# 2_waffling60-MXHS-ISO_matrix.net
KiCad netlist of a schematic drawn in Altium Designer
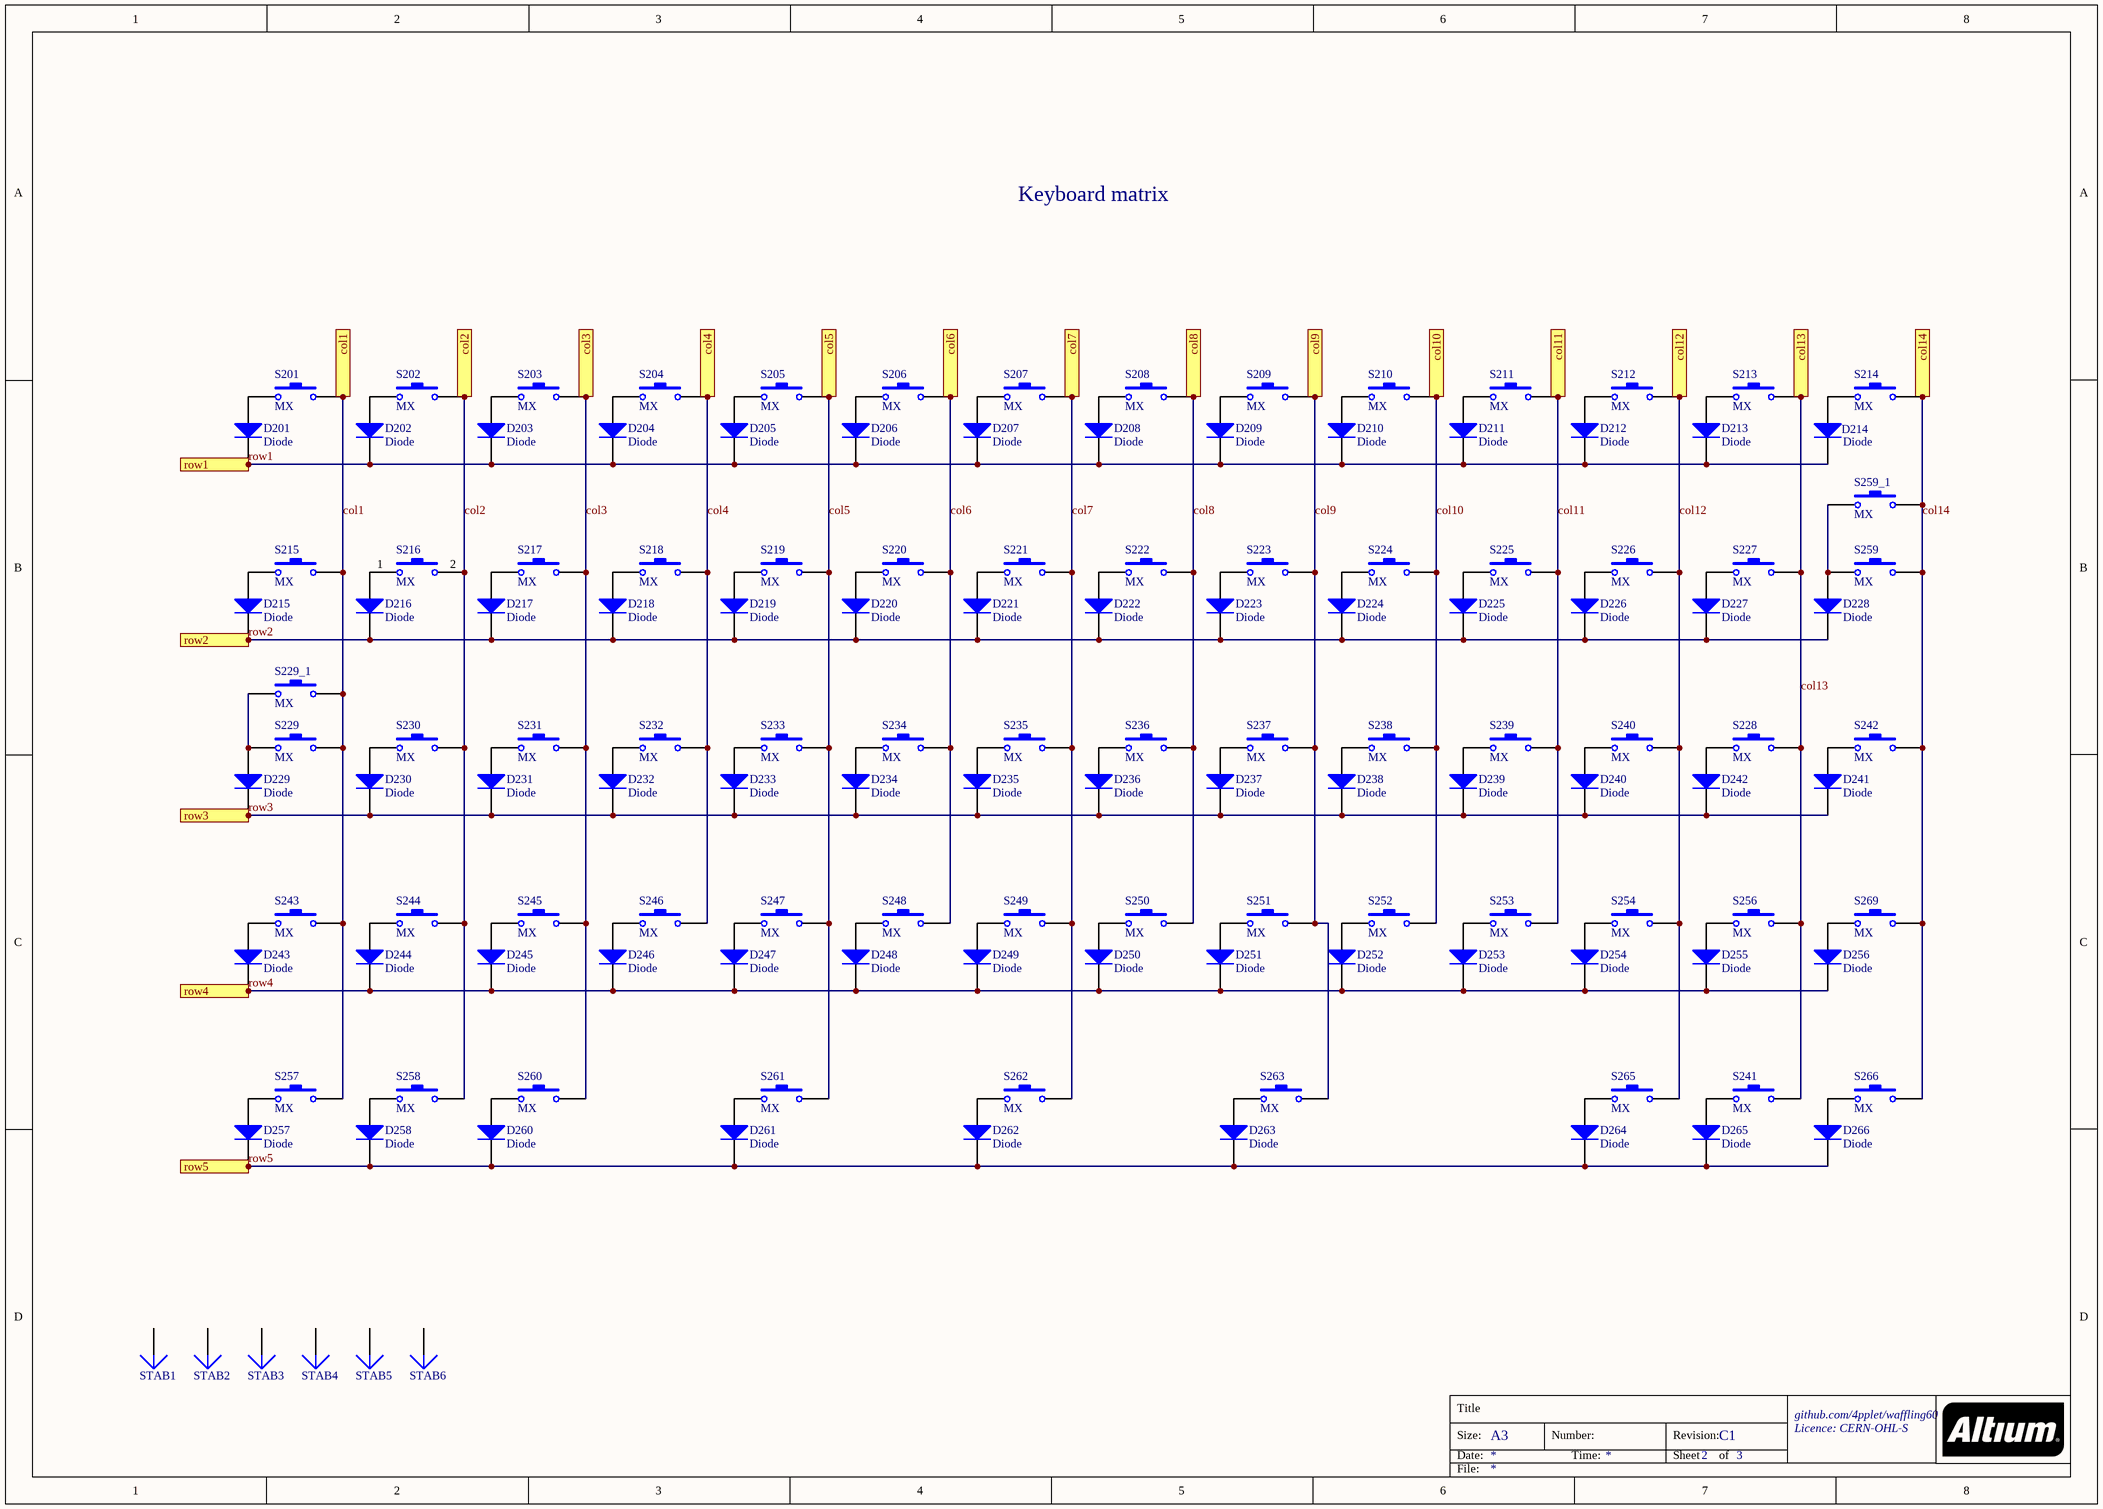
[diagram p0: 2_waffling60-MXHS-ISO_matrix.SchDoc]

(export (version "E")
  (design (tool "Eeschema 10.0.6"))
  (components
    (comp (ref "D201")
      (value "Diode")
      (footprint "SOD-123")
      (description "Default Diode")
      (fields (field (name "LCSC PART #") "C81598") (field (name "MRF.PART") "1N4148W"))
      (libsource (lib "Miscellaneous Devices") (part "Diode"))
    )
    (comp (ref "D202")
      (value "Diode")
      (footprint "SOD-123")
      (description "Default Diode")
      (fields (field (name "LCSC PART #") "C81598") (field (name "MRF.PART") "1N4148W"))
      (libsource (lib "Miscellaneous Devices") (part "Diode"))
    )
    (comp (ref "D203")
      (value "Diode")
      (footprint "SOD-123")
      (description "Default Diode")
      (fields (field (name "LCSC PART #") "C81598") (field (name "MRF.PART") "1N4148W"))
      (libsource (lib "Miscellaneous Devices") (part "Diode"))
    )
    (comp (ref "D204")
      (value "Diode")
      (footprint "SOD-123")
      (description "Default Diode")
      (fields (field (name "LCSC PART #") "C81598") (field (name "MRF.PART") "1N4148W"))
      (libsource (lib "Miscellaneous Devices") (part "Diode"))
    )
    (comp (ref "D205")
      (value "Diode")
      (footprint "SOD-123")
      (description "Default Diode")
      (fields (field (name "LCSC PART #") "C81598") (field (name "MRF.PART") "1N4148W"))
      (libsource (lib "Miscellaneous Devices") (part "Diode"))
    )
    (comp (ref "D206")
      (value "Diode")
      (footprint "SOD-123")
      (description "Default Diode")
      (fields (field (name "LCSC PART #") "C81598") (field (name "MRF.PART") "1N4148W"))
      (libsource (lib "Miscellaneous Devices") (part "Diode"))
    )
    (comp (ref "D207")
      (value "Diode")
      (footprint "SOD-123")
      (description "Default Diode")
      (fields (field (name "LCSC PART #") "C81598") (field (name "MRF.PART") "1N4148W"))
      (libsource (lib "Miscellaneous Devices") (part "Diode"))
    )
    (comp (ref "D208")
      (value "Diode")
      (footprint "SOD-123")
      (description "Default Diode")
      (fields (field (name "LCSC PART #") "C81598") (field (name "MRF.PART") "1N4148W"))
      (libsource (lib "Miscellaneous Devices") (part "Diode"))
    )
    (comp (ref "D209")
      (value "Diode")
      (footprint "SOD-123")
      (description "Default Diode")
      (fields (field (name "LCSC PART #") "C81598") (field (name "MRF.PART") "1N4148W"))
      (libsource (lib "Miscellaneous Devices") (part "Diode"))
    )
    (comp (ref "D210")
      (value "Diode")
      (footprint "SOD-123")
      (description "Default Diode")
      (fields (field (name "LCSC PART #") "C81598") (field (name "MRF.PART") "1N4148W"))
      (libsource (lib "Miscellaneous Devices") (part "Diode"))
    )
    (comp (ref "D211")
      (value "Diode")
      (footprint "SOD-123")
      (description "Default Diode")
      (fields (field (name "LCSC PART #") "C81598") (field (name "MRF.PART") "1N4148W"))
      (libsource (lib "Miscellaneous Devices") (part "Diode"))
    )
    (comp (ref "D212")
      (value "Diode")
      (footprint "SOD-123")
      (description "Default Diode")
      (fields (field (name "LCSC PART #") "C81598") (field (name "MRF.PART") "1N4148W"))
      (libsource (lib "Miscellaneous Devices") (part "Diode"))
    )
    (comp (ref "D213")
      (value "Diode")
      (footprint "SOD-123")
      (description "Default Diode")
      (fields (field (name "LCSC PART #") "C81598") (field (name "MRF.PART") "1N4148W"))
      (libsource (lib "Miscellaneous Devices") (part "Diode"))
    )
    (comp (ref "D214")
      (value "Diode")
      (footprint "SOD-123")
      (description "Default Diode")
      (fields (field (name "LCSC PART #") "C81598") (field (name "MRF.PART") "1N4148W"))
      (libsource (lib "Miscellaneous Devices") (part "Diode"))
    )
    (comp (ref "D215")
      (value "Diode")
      (footprint "SOD-123")
      (description "Default Diode")
      (fields (field (name "LCSC PART #") "C81598") (field (name "MRF.PART") "1N4148W"))
      (libsource (lib "Miscellaneous Devices") (part "Diode"))
    )
    (comp (ref "D216")
      (value "Diode")
      (footprint "SOD-123")
      (description "Default Diode")
      (fields (field (name "LCSC PART #") "C81598") (field (name "MRF.PART") "1N4148W"))
      (libsource (lib "Miscellaneous Devices") (part "Diode"))
    )
    (comp (ref "D217")
      (value "Diode")
      (footprint "SOD-123")
      (description "Default Diode")
      (fields (field (name "LCSC PART #") "C81598") (field (name "MRF.PART") "1N4148W"))
      (libsource (lib "Miscellaneous Devices") (part "Diode"))
    )
    (comp (ref "D218")
      (value "Diode")
      (footprint "SOD-123")
      (description "Default Diode")
      (fields (field (name "LCSC PART #") "C81598") (field (name "MRF.PART") "1N4148W"))
      (libsource (lib "Miscellaneous Devices") (part "Diode"))
    )
    (comp (ref "D219")
      (value "Diode")
      (footprint "SOD-123")
      (description "Default Diode")
      (fields (field (name "LCSC PART #") "C81598") (field (name "MRF.PART") "1N4148W"))
      (libsource (lib "Miscellaneous Devices") (part "Diode"))
    )
    (comp (ref "D220")
      (value "Diode")
      (footprint "SOD-123")
      (description "Default Diode")
      (fields (field (name "LCSC PART #") "C81598") (field (name "MRF.PART") "1N4148W"))
      (libsource (lib "Miscellaneous Devices") (part "Diode"))
    )
    (comp (ref "D221")
      (value "Diode")
      (footprint "SOD-123")
      (description "Default Diode")
      (fields (field (name "LCSC PART #") "C81598") (field (name "MRF.PART") "1N4148W"))
      (libsource (lib "Miscellaneous Devices") (part "Diode"))
    )
    (comp (ref "D222")
      (value "Diode")
      (footprint "SOD-123")
      (description "Default Diode")
      (fields (field (name "LCSC PART #") "C81598") (field (name "MRF.PART") "1N4148W"))
      (libsource (lib "Miscellaneous Devices") (part "Diode"))
    )
    (comp (ref "D223")
      (value "Diode")
      (footprint "SOD-123")
      (description "Default Diode")
      (fields (field (name "LCSC PART #") "C81598") (field (name "MRF.PART") "1N4148W"))
      (libsource (lib "Miscellaneous Devices") (part "Diode"))
    )
    (comp (ref "D224")
      (value "Diode")
      (footprint "SOD-123")
      (description "Default Diode")
      (fields (field (name "LCSC PART #") "C81598") (field (name "MRF.PART") "1N4148W"))
      (libsource (lib "Miscellaneous Devices") (part "Diode"))
    )
    (comp (ref "D225")
      (value "Diode")
      (footprint "SOD-123")
      (description "Default Diode")
      (fields (field (name "LCSC PART #") "C81598") (field (name "MRF.PART") "1N4148W"))
      (libsource (lib "Miscellaneous Devices") (part "Diode"))
    )
    (comp (ref "D226")
      (value "Diode")
      (footprint "SOD-123")
      (description "Default Diode")
      (fields (field (name "LCSC PART #") "C81598") (field (name "MRF.PART") "1N4148W"))
      (libsource (lib "Miscellaneous Devices") (part "Diode"))
    )
    (comp (ref "D227")
      (value "Diode")
      (footprint "SOD-123")
      (description "Default Diode")
      (fields (field (name "LCSC PART #") "C81598") (field (name "MRF.PART") "1N4148W"))
      (libsource (lib "Miscellaneous Devices") (part "Diode"))
    )
    (comp (ref "D228")
      (value "Diode")
      (footprint "SOD-123")
      (description "Default Diode")
      (fields (field (name "LCSC PART #") "C81598") (field (name "MRF.PART") "1N4148W"))
      (libsource (lib "Miscellaneous Devices") (part "Diode"))
    )
    (comp (ref "D229")
      (value "Diode")
      (footprint "SOD-123")
      (description "Default Diode")
      (fields (field (name "LCSC PART #") "C81598") (field (name "MRF.PART") "1N4148W"))
      (libsource (lib "Miscellaneous Devices") (part "Diode"))
    )
    (comp (ref "D230")
      (value "Diode")
      (footprint "SOD-123")
      (description "Default Diode")
      (fields (field (name "LCSC PART #") "C81598") (field (name "MRF.PART") "1N4148W"))
      (libsource (lib "Miscellaneous Devices") (part "Diode"))
    )
    (comp (ref "D231")
      (value "Diode")
      (footprint "SOD-123")
      (description "Default Diode")
      (fields (field (name "LCSC PART #") "C81598") (field (name "MRF.PART") "1N4148W"))
      (libsource (lib "Miscellaneous Devices") (part "Diode"))
    )
    (comp (ref "D232")
      (value "Diode")
      (footprint "SOD-123")
      (description "Default Diode")
      (fields (field (name "LCSC PART #") "C81598") (field (name "MRF.PART") "1N4148W"))
      (libsource (lib "Miscellaneous Devices") (part "Diode"))
    )
    (comp (ref "D233")
      (value "Diode")
      (footprint "SOD-123")
      (description "Default Diode")
      (fields (field (name "LCSC PART #") "C81598") (field (name "MRF.PART") "1N4148W"))
      (libsource (lib "Miscellaneous Devices") (part "Diode"))
    )
    (comp (ref "D234")
      (value "Diode")
      (footprint "SOD-123")
      (description "Default Diode")
      (fields (field (name "LCSC PART #") "C81598") (field (name "MRF.PART") "1N4148W"))
      (libsource (lib "Miscellaneous Devices") (part "Diode"))
    )
    (comp (ref "D235")
      (value "Diode")
      (footprint "SOD-123")
      (description "Default Diode")
      (fields (field (name "LCSC PART #") "C81598") (field (name "MRF.PART") "1N4148W"))
      (libsource (lib "Miscellaneous Devices") (part "Diode"))
    )
    (comp (ref "D236")
      (value "Diode")
      (footprint "SOD-123")
      (description "Default Diode")
      (fields (field (name "LCSC PART #") "C81598") (field (name "MRF.PART") "1N4148W"))
      (libsource (lib "Miscellaneous Devices") (part "Diode"))
    )
    (comp (ref "D237")
      (value "Diode")
      (footprint "SOD-123")
      (description "Default Diode")
      (fields (field (name "LCSC PART #") "C81598") (field (name "MRF.PART") "1N4148W"))
      (libsource (lib "Miscellaneous Devices") (part "Diode"))
    )
    (comp (ref "D238")
      (value "Diode")
      (footprint "SOD-123")
      (description "Default Diode")
      (fields (field (name "LCSC PART #") "C81598") (field (name "MRF.PART") "1N4148W"))
      (libsource (lib "Miscellaneous Devices") (part "Diode"))
    )
    (comp (ref "D239")
      (value "Diode")
      (footprint "SOD-123")
      (description "Default Diode")
      (fields (field (name "LCSC PART #") "C81598") (field (name "MRF.PART") "1N4148W"))
      (libsource (lib "Miscellaneous Devices") (part "Diode"))
    )
    (comp (ref "D240")
      (value "Diode")
      (footprint "SOD-123")
      (description "Default Diode")
      (fields (field (name "LCSC PART #") "C81598") (field (name "MRF.PART") "1N4148W"))
      (libsource (lib "Miscellaneous Devices") (part "Diode"))
    )
    (comp (ref "D241")
      (value "Diode")
      (footprint "SOD-123")
      (description "Default Diode")
      (fields (field (name "LCSC PART #") "C81598") (field (name "MRF.PART") "1N4148W"))
      (libsource (lib "Miscellaneous Devices") (part "Diode"))
    )
    (comp (ref "D242")
      (value "Diode")
      (footprint "SOD-123")
      (description "Default Diode")
      (fields (field (name "LCSC PART #") "C81598") (field (name "MRF.PART") "1N4148W"))
      (libsource (lib "Miscellaneous Devices") (part "Diode"))
    )
    (comp (ref "D243")
      (value "Diode")
      (footprint "SOD-123")
      (description "Default Diode")
      (fields (field (name "LCSC PART #") "C81598") (field (name "MRF.PART") "1N4148W"))
      (libsource (lib "Miscellaneous Devices") (part "Diode"))
    )
    (comp (ref "D244")
      (value "Diode")
      (footprint "SOD-123")
      (description "Default Diode")
      (fields (field (name "LCSC PART #") "C81598") (field (name "MRF.PART") "1N4148W"))
      (libsource (lib "Miscellaneous Devices") (part "Diode"))
    )
    (comp (ref "D245")
      (value "Diode")
      (footprint "SOD-123")
      (description "Default Diode")
      (fields (field (name "LCSC PART #") "C81598") (field (name "MRF.PART") "1N4148W"))
      (libsource (lib "Miscellaneous Devices") (part "Diode"))
    )
    (comp (ref "D246")
      (value "Diode")
      (footprint "SOD-123")
      (description "Default Diode")
      (fields (field (name "LCSC PART #") "C81598") (field (name "MRF.PART") "1N4148W"))
      (libsource (lib "Miscellaneous Devices") (part "Diode"))
    )
    (comp (ref "D247")
      (value "Diode")
      (footprint "SOD-123")
      (description "Default Diode")
      (fields (field (name "LCSC PART #") "C81598") (field (name "MRF.PART") "1N4148W"))
      (libsource (lib "Miscellaneous Devices") (part "Diode"))
    )
    (comp (ref "D248")
      (value "Diode")
      (footprint "SOD-123")
      (description "Default Diode")
      (fields (field (name "LCSC PART #") "C81598") (field (name "MRF.PART") "1N4148W"))
      (libsource (lib "Miscellaneous Devices") (part "Diode"))
    )
    (comp (ref "D249")
      (value "Diode")
      (footprint "SOD-123")
      (description "Default Diode")
      (fields (field (name "LCSC PART #") "C81598") (field (name "MRF.PART") "1N4148W"))
      (libsource (lib "Miscellaneous Devices") (part "Diode"))
    )
    (comp (ref "D250")
      (value "Diode")
      (footprint "SOD-123")
      (description "Default Diode")
      (fields (field (name "LCSC PART #") "C81598") (field (name "MRF.PART") "1N4148W"))
      (libsource (lib "Miscellaneous Devices") (part "Diode"))
    )
    (comp (ref "D251")
      (value "Diode")
      (footprint "SOD-123")
      (description "Default Diode")
      (fields (field (name "LCSC PART #") "C81598") (field (name "MRF.PART") "1N4148W"))
      (libsource (lib "Miscellaneous Devices") (part "Diode"))
    )
    (comp (ref "D252")
      (value "Diode")
      (footprint "SOD-123")
      (description "Default Diode")
      (fields (field (name "LCSC PART #") "C81598") (field (name "MRF.PART") "1N4148W"))
      (libsource (lib "Miscellaneous Devices") (part "Diode"))
    )
    (comp (ref "D253")
      (value "Diode")
      (footprint "SOD-123")
      (description "Default Diode")
      (fields (field (name "LCSC PART #") "C81598") (field (name "MRF.PART") "1N4148W"))
      (libsource (lib "Miscellaneous Devices") (part "Diode"))
    )
    (comp (ref "D254")
      (value "Diode")
      (footprint "SOD-123")
      (description "Default Diode")
      (fields (field (name "LCSC PART #") "C81598") (field (name "MRF.PART") "1N4148W"))
      (libsource (lib "Miscellaneous Devices") (part "Diode"))
    )
    (comp (ref "D255")
      (value "Diode")
      (footprint "SOD-123")
      (description "Default Diode")
      (fields (field (name "LCSC PART #") "C81598") (field (name "MRF.PART") "1N4148W"))
      (libsource (lib "Miscellaneous Devices") (part "Diode"))
    )
    (comp (ref "D256")
      (value "Diode")
      (footprint "SOD-123")
      (description "Default Diode")
      (fields (field (name "LCSC PART #") "C81598") (field (name "MRF.PART") "1N4148W"))
      (libsource (lib "Miscellaneous Devices") (part "Diode"))
    )
    (comp (ref "D257")
      (value "Diode")
      (footprint "SOD-123")
      (description "Default Diode")
      (fields (field (name "LCSC PART #") "C81598") (field (name "MRF.PART") "1N4148W"))
      (libsource (lib "Miscellaneous Devices") (part "Diode"))
    )
    (comp (ref "D258")
      (value "Diode")
      (footprint "SOD-123")
      (description "Default Diode")
      (fields (field (name "LCSC PART #") "C81598") (field (name "MRF.PART") "1N4148W"))
      (libsource (lib "Miscellaneous Devices") (part "Diode"))
    )
    (comp (ref "D260")
      (value "Diode")
      (footprint "SOD-123")
      (description "Default Diode")
      (fields (field (name "LCSC PART #") "C81598") (field (name "MRF.PART") "1N4148W"))
      (libsource (lib "Miscellaneous Devices") (part "Diode"))
    )
    (comp (ref "D261")
      (value "Diode")
      (footprint "SOD-123")
      (description "Default Diode")
      (fields (field (name "LCSC PART #") "C81598") (field (name "MRF.PART") "1N4148W"))
      (libsource (lib "Miscellaneous Devices") (part "Diode"))
    )
    (comp (ref "D262")
      (value "Diode")
      (footprint "SOD-123")
      (description "Default Diode")
      (fields (field (name "LCSC PART #") "C81598") (field (name "MRF.PART") "1N4148W"))
      (libsource (lib "Miscellaneous Devices") (part "Diode"))
    )
    (comp (ref "D263")
      (value "Diode")
      (footprint "SOD-123")
      (description "Default Diode")
      (fields (field (name "LCSC PART #") "C81598") (field (name "MRF.PART") "1N4148W"))
      (libsource (lib "Miscellaneous Devices") (part "Diode"))
    )
    (comp (ref "D264")
      (value "Diode")
      (footprint "SOD-123")
      (description "Default Diode")
      (fields (field (name "LCSC PART #") "C81598") (field (name "MRF.PART") "1N4148W"))
      (libsource (lib "Miscellaneous Devices") (part "Diode"))
    )
    (comp (ref "D265")
      (value "Diode")
      (footprint "SOD-123")
      (description "Default Diode")
      (fields (field (name "LCSC PART #") "C81598") (field (name "MRF.PART") "1N4148W"))
      (libsource (lib "Miscellaneous Devices") (part "Diode"))
    )
    (comp (ref "D266")
      (value "Diode")
      (footprint "SOD-123")
      (description "Default Diode")
      (fields (field (name "LCSC PART #") "C81598") (field (name "MRF.PART") "1N4148W"))
      (libsource (lib "Miscellaneous Devices") (part "Diode"))
    )
    (comp (ref "S201")
      (value "MX")
      (footprint "MXHS-switch - 1U Top layer - AS2")
      (description "Switch")
      (fields (field (name "LCSC PART #") "C2803348") (field (name "MRF.PART") "CPG151101S11"))
      (libsource (lib "Miscellaneous Devices") (part "SW-PB"))
    )
    (comp (ref "S202")
      (value "MX")
      (footprint "MXHS-switch - 1U Top layer - switched pol AS2")
      (description "Switch")
      (fields (field (name "LCSC PART #") "C2803348") (field (name "MRF.PART") "CPG151101S11"))
      (libsource (lib "Miscellaneous Devices") (part "SW-PB"))
    )
    (comp (ref "S203")
      (value "MX")
      (footprint "MXHS-switch - 1U Top layer - AS2")
      (description "Switch")
      (fields (field (name "LCSC PART #") "C2803348") (field (name "MRF.PART") "CPG151101S11"))
      (libsource (lib "Miscellaneous Devices") (part "SW-PB"))
    )
    (comp (ref "S204")
      (value "MX")
      (footprint "MXHS-switch - 1U Top layer - switched pol AS2")
      (description "Switch")
      (fields (field (name "LCSC PART #") "C2803348") (field (name "MRF.PART") "CPG151101S11"))
      (libsource (lib "Miscellaneous Devices") (part "SW-PB"))
    )
    (comp (ref "S205")
      (value "MX")
      (footprint "MXHS-switch - 1U Top layer - AS2")
      (description "Switch")
      (fields (field (name "LCSC PART #") "C2803348") (field (name "MRF.PART") "CPG151101S11"))
      (libsource (lib "Miscellaneous Devices") (part "SW-PB"))
    )
    (comp (ref "S206")
      (value "MX")
      (footprint "MXHS-switch - 1U Top layer - AS2")
      (description "Switch")
      (fields (field (name "LCSC PART #") "C2803348") (field (name "MRF.PART") "CPG151101S11"))
      (libsource (lib "Miscellaneous Devices") (part "SW-PB"))
    )
    (comp (ref "S207")
      (value "MX")
      (footprint "MXHS-switch - 1U Top layer - AS2")
      (description "Switch")
      (fields (field (name "LCSC PART #") "C2803348") (field (name "MRF.PART") "CPG151101S11"))
      (libsource (lib "Miscellaneous Devices") (part "SW-PB"))
    )
    (comp (ref "S208")
      (value "MX")
      (footprint "MXHS-switch - 1U Top layer - AS2")
      (description "Switch")
      (fields (field (name "LCSC PART #") "C2803348") (field (name "MRF.PART") "CPG151101S11"))
      (libsource (lib "Miscellaneous Devices") (part "SW-PB"))
    )
    (comp (ref "S209")
      (value "MX")
      (footprint "MXHS-switch - 1U Top layer - AS2")
      (description "Switch")
      (fields (field (name "LCSC PART #") "C2803348") (field (name "MRF.PART") "CPG151101S11"))
      (libsource (lib "Miscellaneous Devices") (part "SW-PB"))
    )
    (comp (ref "S210")
      (value "MX")
      (footprint "MXHS-switch - 1U Top layer - AS2")
      (description "Switch")
      (fields (field (name "LCSC PART #") "C2803348") (field (name "MRF.PART") "CPG151101S11"))
      (libsource (lib "Miscellaneous Devices") (part "SW-PB"))
    )
    (comp (ref "S211")
      (value "MX")
      (footprint "MXHS-switch - 1U Top layer - switched pol AS2")
      (description "Switch")
      (fields (field (name "LCSC PART #") "C2803348") (field (name "MRF.PART") "CPG151101S11"))
      (libsource (lib "Miscellaneous Devices") (part "SW-PB"))
    )
    (comp (ref "S212")
      (value "MX")
      (footprint "MXHS-switch - 1U Top layer - AS2")
      (description "Switch")
      (fields (field (name "LCSC PART #") "C2803348") (field (name "MRF.PART") "CPG151101S11"))
      (libsource (lib "Miscellaneous Devices") (part "SW-PB"))
    )
    (comp (ref "S213")
      (value "MX")
      (footprint "MXHS-switch - 1U Top layer - AS2")
      (description "Switch")
      (fields (field (name "LCSC PART #") "C2803348") (field (name "MRF.PART") "CPG151101S11"))
      (libsource (lib "Miscellaneous Devices") (part "SW-PB"))
    )
    (comp (ref "S214")
      (value "MX")
      (footprint "MXHS-switch - 1U Top layer - AS2 - S2")
      (description "Switch")
      (fields (field (name "LCSC PART #") "C2803348") (field (name "MRF.PART") "CPG151101S11"))
      (libsource (lib "Miscellaneous Devices") (part "SW-PB"))
    )
    (comp (ref "S215")
      (value "MX")
      (footprint "MXHS-switch - 1U Top layer - AS2")
      (description "TAB")
      (fields (field (name "LCSC PART #") "C2803348") (field (name "MRF.PART") "CPG151101S11"))
      (libsource (lib "Miscellaneous Devices") (part "SW-PB"))
    )
    (comp (ref "S216")
      (value "MX")
      (footprint "MXHS-switch - 1U Top layer - switched pol AS2")
      (description "Switch")
      (fields (field (name "LCSC PART #") "C2803348") (field (name "MRF.PART") "CPG151101S11"))
      (libsource (lib "") (part "SW-PB_1"))
    )
    (comp (ref "S217")
      (value "MX")
      (footprint "MXHS-switch - 1U Top layer - AS2")
      (description "Switch")
      (fields (field (name "LCSC PART #") "C2803348") (field (name "MRF.PART") "CPG151101S11"))
      (libsource (lib "Miscellaneous Devices") (part "SW-PB"))
    )
    (comp (ref "S218")
      (value "MX")
      (footprint "MXHS-switch - 1U Top layer - AS2")
      (description "Switch")
      (fields (field (name "LCSC PART #") "C2803348") (field (name "MRF.PART") "CPG151101S11"))
      (libsource (lib "Miscellaneous Devices") (part "SW-PB"))
    )
    (comp (ref "S219")
      (value "MX")
      (footprint "MXHS-switch - 1U Top layer - AS2")
      (description "Switch")
      (fields (field (name "LCSC PART #") "C2803348") (field (name "MRF.PART") "CPG151101S11"))
      (libsource (lib "Miscellaneous Devices") (part "SW-PB"))
    )
    (comp (ref "S220")
      (value "MX")
      (footprint "MXHS-switch - 1U Top layer - switched pol AS2")
      (description "Switch")
      (fields (field (name "LCSC PART #") "C2803348") (field (name "MRF.PART") "CPG151101S11"))
      (libsource (lib "Miscellaneous Devices") (part "SW-PB"))
    )
    (comp (ref "S221")
      (value "MX")
      (footprint "MXHS-switch - 1U Top layer - AS2")
      (description "Switch")
      (fields (field (name "LCSC PART #") "C2803348") (field (name "MRF.PART") "CPG151101S11"))
      (libsource (lib "Miscellaneous Devices") (part "SW-PB"))
    )
    (comp (ref "S222")
      (value "MX")
      (footprint "MXHS-switch - 1U Top layer - switched pol AS2")
      (description "Switch")
      (fields (field (name "LCSC PART #") "C2803348") (field (name "MRF.PART") "CPG151101S11"))
      (libsource (lib "Miscellaneous Devices") (part "SW-PB"))
    )
    (comp (ref "S223")
      (value "MX")
      (footprint "MXHS-switch - 1U Top layer - AS2")
      (description "Switch")
      (fields (field (name "LCSC PART #") "C2803348") (field (name "MRF.PART") "CPG151101S11"))
      (libsource (lib "Miscellaneous Devices") (part "SW-PB"))
    )
    (comp (ref "S224")
      (value "MX")
      (footprint "MXHS-switch - 1U Top layer - AS2")
      (description "Switch")
      (fields (field (name "LCSC PART #") "C2803348") (field (name "MRF.PART") "CPG151101S11"))
      (libsource (lib "Miscellaneous Devices") (part "SW-PB"))
    )
    (comp (ref "S225")
      (value "MX")
      (footprint "MXHS-switch - 1U Top layer - AS2")
      (description "Switch")
      (fields (field (name "LCSC PART #") "C2803348") (field (name "MRF.PART") "CPG151101S11"))
      (libsource (lib "Miscellaneous Devices") (part "SW-PB"))
    )
    (comp (ref "S226")
      (value "MX")
      (footprint "MXHS-switch - 1U Top layer - AS2")
      (description "Switch")
      (fields (field (name "LCSC PART #") "C2803348") (field (name "MRF.PART") "CPG151101S11"))
      (libsource (lib "Miscellaneous Devices") (part "SW-PB"))
    )
    (comp (ref "S227")
      (value "MX")
      (footprint "MXHS-switch - 1U Top layer - switched pol AS2")
      (description "Switch")
      (fields (field (name "LCSC PART #") "C2803348") (field (name "MRF.PART") "CPG151101S11"))
      (libsource (lib "Miscellaneous Devices") (part "SW-PB"))
    )
    (comp (ref "S228")
      (value "MX")
      (footprint "MXHS-switch - 1U Top layer - switched pol AS2")
      (description "Switch")
      (fields (field (name "LCSC PART #") "C2803348") (field (name "MRF.PART") "CPG151101S11"))
      (libsource (lib "Miscellaneous Devices") (part "SW-PB"))
    )
    (comp (ref "S229")
      (value "MX")
      (footprint "MXHS-switch - 1U Top layer - AS2")
      (description "Switch")
      (fields (field (name "LCSC PART #") "C2803348") (field (name "MRF.PART") "CPG151101S11"))
      (libsource (lib "Miscellaneous Devices") (part "SW-PB"))
    )
    (comp (ref "S229_1")
      (value "MX")
      (footprint "MXHS-switch - 1U Top layer - AS2")
      (description "Switch")
      (fields (field (name "LCSC PART #") "C2803348") (field (name "MRF.PART") "CPG151101S11"))
      (libsource (lib "Miscellaneous Devices") (part "SW-PB"))
    )
    (comp (ref "S230")
      (value "MX")
      (footprint "MXHS-switch - 1U Top layer - switched pol AS2")
      (description "Switch")
      (fields (field (name "LCSC PART #") "C2803348") (field (name "MRF.PART") "CPG151101S11"))
      (libsource (lib "Miscellaneous Devices") (part "SW-PB"))
    )
    (comp (ref "S231")
      (value "MX")
      (footprint "MXHS-switch - 1U Top layer - AS2")
      (description "Switch")
      (fields (field (name "LCSC PART #") "C2803348") (field (name "MRF.PART") "CPG151101S11"))
      (libsource (lib "Miscellaneous Devices") (part "SW-PB"))
    )
    (comp (ref "S232")
      (value "MX")
      (footprint "MXHS-switch - 1U Top layer - AS2")
      (description "Switch")
      (fields (field (name "LCSC PART #") "C2803348") (field (name "MRF.PART") "CPG151101S11"))
      (libsource (lib "Miscellaneous Devices") (part "SW-PB"))
    )
    (comp (ref "S233")
      (value "MX")
      (footprint "MXHS-switch - 1U Top layer - AS2")
      (description "Switch")
      (fields (field (name "LCSC PART #") "C2803348") (field (name "MRF.PART") "CPG151101S11"))
      (libsource (lib "Miscellaneous Devices") (part "SW-PB"))
    )
    (comp (ref "S234")
      (value "MX")
      (footprint "MXHS-switch - 1U Top layer - switched pol AS2")
      (description "Switch")
      (fields (field (name "LCSC PART #") "C2803348") (field (name "MRF.PART") "CPG151101S11"))
      (libsource (lib "Miscellaneous Devices") (part "SW-PB"))
    )
    (comp (ref "S235")
      (value "MX")
      (footprint "MXHS-switch - 1U Top layer - AS2 - S2")
      (description "Switch")
      (fields (field (name "LCSC PART #") "C2803348") (field (name "MRF.PART") "CPG151101S11"))
      (libsource (lib "Miscellaneous Devices") (part "SW-PB"))
    )
    (comp (ref "S236")
      (value "MX")
      (footprint "MXHS-switch - 1U Top layer - AS2")
      (description "Switch")
      (fields (field (name "LCSC PART #") "C2803348") (field (name "MRF.PART") "CPG151101S11"))
      (libsource (lib "Miscellaneous Devices") (part "SW-PB"))
    )
    (comp (ref "S237")
      (value "MX")
      (footprint "MXHS-switch - 1U Top layer - AS2")
      (description "Switch")
      (fields (field (name "LCSC PART #") "C2803348") (field (name "MRF.PART") "CPG151101S11"))
      (libsource (lib "Miscellaneous Devices") (part "SW-PB"))
    )
    (comp (ref "S238")
      (value "MX")
      (footprint "MXHS-switch - 1U Top layer - AS2")
      (description "Switch")
      (fields (field (name "LCSC PART #") "C2803348") (field (name "MRF.PART") "CPG151101S11"))
      (libsource (lib "Miscellaneous Devices") (part "SW-PB"))
    )
    (comp (ref "S239")
      (value "MX")
      (footprint "MXHS-switch - 1U Top layer - AS2")
      (description "Switch")
      (fields (field (name "LCSC PART #") "C2803348") (field (name "MRF.PART") "CPG151101S11"))
      (libsource (lib "Miscellaneous Devices") (part "SW-PB"))
    )
    (comp (ref "S240")
      (value "MX")
      (footprint "MXHS-switch - 1U Top layer - AS2")
      (description "Switch")
      (fields (field (name "LCSC PART #") "C2803348") (field (name "MRF.PART") "CPG151101S11"))
      (libsource (lib "Miscellaneous Devices") (part "SW-PB"))
    )
    (comp (ref "S241")
      (value "MX")
      (footprint "MXHS-switch - 1U Top layer - AS2")
      (description "Switch")
      (fields (field (name "LCSC PART #") "C2803348") (field (name "MRF.PART") "CPG151101S11"))
      (libsource (lib "Miscellaneous Devices") (part "SW-PB"))
    )
    (comp (ref "S242")
      (value "MX")
      (footprint "MXHS-switch - 1U Top layer - switched pol AS2")
      (description "Switch")
      (fields (field (name "LCSC PART #") "C2803348") (field (name "MRF.PART") "CPG151101S11"))
      (libsource (lib "Miscellaneous Devices") (part "SW-PB"))
    )
    (comp (ref "S243")
      (value "MX")
      (footprint "MXHS-switch - 1U Top layer - AS2")
      (description "Switch")
      (fields (field (name "LCSC PART #") "C2803348") (field (name "MRF.PART") "CPG151101S11"))
      (libsource (lib "Miscellaneous Devices") (part "SW-PB"))
    )
    (comp (ref "S244")
      (value "MX")
      (footprint "MXHS-switch - 1U Top layer - switched pol AS2")
      (description "Switch")
      (fields (field (name "LCSC PART #") "C2803348") (field (name "MRF.PART") "CPG151101S11"))
      (libsource (lib "Miscellaneous Devices") (part "SW-PB"))
    )
    (comp (ref "S245")
      (value "MX")
      (footprint "MXHS-switch - 1U Top layer - AS2")
      (description "Switch")
      (fields (field (name "LCSC PART #") "C2803348") (field (name "MRF.PART") "CPG151101S11"))
      (libsource (lib "Miscellaneous Devices") (part "SW-PB"))
    )
    (comp (ref "S246")
      (value "MX")
      (footprint "MXHS-switch - 1U Top layer - AS2")
      (description "Switch")
      (fields (field (name "LCSC PART #") "C2803348") (field (name "MRF.PART") "CPG151101S11"))
      (libsource (lib "Miscellaneous Devices") (part "SW-PB"))
    )
    (comp (ref "S247")
      (value "MX")
      (footprint "MXHS-switch - 1U Top layer - AS2")
      (description "Switch")
      (fields (field (name "LCSC PART #") "C2803348") (field (name "MRF.PART") "CPG151101S11"))
      (libsource (lib "Miscellaneous Devices") (part "SW-PB"))
    )
    (comp (ref "S248")
      (value "MX")
      (footprint "MXHS-switch - 1U Top layer - AS2")
      (description "Switch")
      (fields (field (name "LCSC PART #") "C2803348") (field (name "MRF.PART") "CPG151101S11"))
      (libsource (lib "Miscellaneous Devices") (part "SW-PB"))
    )
    (comp (ref "S249")
      (value "MX")
      (footprint "MXHS-switch - 1U Top layer - AS2")
      (description "Switch")
      (fields (field (name "LCSC PART #") "C2803348") (field (name "MRF.PART") "CPG151101S11"))
      (libsource (lib "Miscellaneous Devices") (part "SW-PB"))
    )
    (comp (ref "S250")
      (value "MX")
      (footprint "MXHS-switch - 1U Top layer - AS2")
      (description "Switch")
      (fields (field (name "LCSC PART #") "C2803348") (field (name "MRF.PART") "CPG151101S11"))
      (libsource (lib "Miscellaneous Devices") (part "SW-PB"))
    )
    (comp (ref "S251")
      (value "MX")
      (footprint "MXHS-switch - 1U Top layer - AS2")
      (description "Switch")
      (fields (field (name "LCSC PART #") "C2803348") (field (name "MRF.PART") "CPG151101S11"))
      (libsource (lib "Miscellaneous Devices") (part "SW-PB"))
    )
    (comp (ref "S252")
      (value "MX")
      (footprint "MXHS-switch - 1U Top layer - AS2")
      (description "Switch")
      (fields (field (name "LCSC PART #") "C2803348") (field (name "MRF.PART") "CPG151101S11"))
      (libsource (lib "Miscellaneous Devices") (part "SW-PB"))
    )
    (comp (ref "S253")
      (value "MX")
      (footprint "MXHS-switch - 1U Top layer - AS2")
      (description "Switch")
      (fields (field (name "LCSC PART #") "C2803348") (field (name "MRF.PART") "CPG151101S11"))
      (libsource (lib "Miscellaneous Devices") (part "SW-PB"))
    )
    (comp (ref "S254")
      (value "MX")
      (footprint "MXHS-switch - 1U Top layer - AS2")
      (description "Switch")
      (fields (field (name "LCSC PART #") "C2803348") (field (name "MRF.PART") "CPG151101S11"))
      (libsource (lib "Miscellaneous Devices") (part "SW-PB"))
    )
    (comp (ref "S256")
      (value "MX")
      (footprint "MXHS-switch - 1U Top layer - AS2")
      (description "Switch")
      (fields (field (name "LCSC PART #") "C2803348") (field (name "MRF.PART") "CPG151101S11"))
      (libsource (lib "Miscellaneous Devices") (part "SW-PB"))
    )
    (comp (ref "S257")
      (value "MX")
      (footprint "MXHS-switch - 1U Top layer - switched pol AS2")
      (description "Switch")
      (fields (field (name "LCSC PART #") "C2803348") (field (name "MRF.PART") "CPG151101S11"))
      (libsource (lib "Miscellaneous Devices") (part "SW-PB"))
    )
    (comp (ref "S258")
      (value "MX")
      (footprint "MXHS-switch - 1U Top layer - AS2")
      (description "Switch")
      (fields (field (name "LCSC PART #") "C2803348") (field (name "MRF.PART") "CPG151101S11"))
      (libsource (lib "Miscellaneous Devices") (part "SW-PB"))
    )
    (comp (ref "S259")
      (value "MX")
      (footprint "MXHS-switch - 1U Top layer - AS2 - S2")
      (description "Switch")
      (fields (field (name "LCSC PART #") "C2803348") (field (name "MRF.PART") "CPG151101S11"))
      (libsource (lib "Miscellaneous Devices") (part "SW-PB"))
    )
    (comp (ref "S259_1")
      (value "MX")
      (footprint "MXHS-switch - 1U Top layer - AS2 - S1")
      (description "Switch")
      (fields (field (name "LCSC PART #") "C2803348") (field (name "MRF.PART") "CPG151101S11"))
      (libsource (lib "Miscellaneous Devices") (part "SW-PB"))
    )
    (comp (ref "S260")
      (value "MX")
      (footprint "MXHS-switch - 1U Top layer - AS2")
      (description "Switch")
      (fields (field (name "LCSC PART #") "C2803348") (field (name "MRF.PART") "CPG151101S11"))
      (libsource (lib "Miscellaneous Devices") (part "SW-PB"))
    )
    (comp (ref "S261")
      (value "MX")
      (footprint "MXHS-switch - 1U Top layer - switched pol AS2")
      (description "Switch")
      (fields (field (name "LCSC PART #") "C2803348") (field (name "MRF.PART") "CPG151101S11"))
      (libsource (lib "Miscellaneous Devices") (part "SW-PB"))
    )
    (comp (ref "S262")
      (value "MX")
      (footprint "MXHS-switch - 1U Top layer - switched pol AS2")
      (description "Switch")
      (fields (field (name "LCSC PART #") "C2803348") (field (name "MRF.PART") "CPG151101S11"))
      (libsource (lib "Miscellaneous Devices") (part "SW-PB"))
    )
    (comp (ref "S263")
      (value "MX")
      (footprint "MXHS-switch - 1U Top layer - switched pol AS2")
      (description "Switch")
      (fields (field (name "LCSC PART #") "C2803348") (field (name "MRF.PART") "CPG151101S11"))
      (libsource (lib "Miscellaneous Devices") (part "SW-PB"))
    )
    (comp (ref "S265")
      (value "MX")
      (footprint "MXHS-switch - 1U Top layer - switched pol AS2")
      (description "Switch")
      (fields (field (name "LCSC PART #") "C2803348") (field (name "MRF.PART") "CPG151101S11"))
      (libsource (lib "Miscellaneous Devices") (part "SW-PB"))
    )
    (comp (ref "S266")
      (value "MX")
      (footprint "MXHS-switch - 1U Top layer - switched pol AS2")
      (description "Switch")
      (fields (field (name "LCSC PART #") "C2803348") (field (name "MRF.PART") "CPG151101S11"))
      (libsource (lib "Miscellaneous Devices") (part "SW-PB"))
    )
    (comp (ref "S269")
      (value "MX")
      (footprint "MXHS-switch - 1U Top layer - AS2")
      (description "Switch")
      (fields (field (name "LCSC PART #") "C2803348") (field (name "MRF.PART") "CPG151101S11"))
      (libsource (lib "Miscellaneous Devices") (part "SW-PB"))
    )
    (comp (ref "STAB1")
      (value "Plug")
      (footprint "Stab 2u")
      (libsource (lib "Miscellaneous Connectors") (part "Plug"))
    )
    (comp (ref "STAB2")
      (value "Plug")
      (footprint "Stab 2u")
      (libsource (lib "Miscellaneous Connectors") (part "Plug"))
    )
    (comp (ref "STAB3")
      (value "Plug")
      (footprint "Stab 7U")
      (libsource (lib "Miscellaneous Connectors") (part "Plug"))
    )
    (comp (ref "STAB4")
      (value "Plug")
      (footprint "Stab 10U")
      (libsource (lib "Miscellaneous Connectors") (part "Plug"))
    )
    (comp (ref "STAB5")
      (value "Plug")
      (footprint "Stab 3u")
      (libsource (lib "Miscellaneous Connectors") (part "Plug"))
    )
    (comp (ref "STAB6")
      (value "Plug")
      (footprint "Stab 3u")
      (libsource (lib "Miscellaneous Connectors") (part "Plug"))
    )
  )
  (nets
    (net (code "1") (name "/col1") (class "Default")
      (node (ref "S201") (pin "2") (pinfunction "2_2") (pintype "passive"))
      (node (ref "S215") (pin "2") (pinfunction "2_2") (pintype "passive"))
      (node (ref "S229") (pin "2") (pinfunction "2_2") (pintype "passive"))
      (node (ref "S229_1") (pin "1") (pinfunction "1_1") (pintype "passive"))
      (node (ref "S243") (pin "2") (pinfunction "2_2") (pintype "passive"))
      (node (ref "S257") (pin "1") (pinfunction "1_1") (pintype "passive"))
    )
    (net (code "2") (name "/col2") (class "Default")
      (node (ref "S202") (pin "2") (pinfunction "2_2") (pintype "passive"))
      (node (ref "S216") (pin "2") (pinfunction "2_2") (pintype "passive"))
      (node (ref "S230") (pin "2") (pinfunction "2_2") (pintype "passive"))
      (node (ref "S244") (pin "1") (pinfunction "1_1") (pintype "passive"))
      (node (ref "S258") (pin "2") (pinfunction "2_2") (pintype "passive"))
    )
    (net (code "3") (name "/col3") (class "Default")
      (node (ref "S203") (pin "2") (pinfunction "2_2") (pintype "passive"))
      (node (ref "S217") (pin "2") (pinfunction "2_2") (pintype "passive"))
      (node (ref "S231") (pin "2") (pinfunction "2_2") (pintype "passive"))
      (node (ref "S245") (pin "2") (pinfunction "2_2") (pintype "passive"))
      (node (ref "S260") (pin "2") (pinfunction "2_2") (pintype "passive"))
    )
    (net (code "4") (name "/col4") (class "Default")
      (node (ref "S204") (pin "2") (pinfunction "2_2") (pintype "passive"))
      (node (ref "S218") (pin "2") (pinfunction "2_2") (pintype "passive"))
      (node (ref "S232") (pin "2") (pinfunction "2_2") (pintype "passive"))
      (node (ref "S246") (pin "2") (pinfunction "2_2") (pintype "passive"))
    )
    (net (code "5") (name "/col5") (class "Default")
      (node (ref "S205") (pin "2") (pinfunction "2_2") (pintype "passive"))
      (node (ref "S219") (pin "2") (pinfunction "2_2") (pintype "passive"))
      (node (ref "S233") (pin "2") (pinfunction "2_2") (pintype "passive"))
      (node (ref "S247") (pin "2") (pinfunction "2_2") (pintype "passive"))
      (node (ref "S261") (pin "2") (pinfunction "2_2") (pintype "passive"))
    )
    (net (code "6") (name "/col6") (class "Default")
      (node (ref "S206") (pin "2") (pinfunction "2_2") (pintype "passive"))
      (node (ref "S220") (pin "2") (pinfunction "2_2") (pintype "passive"))
      (node (ref "S234") (pin "2") (pinfunction "2_2") (pintype "passive"))
      (node (ref "S248") (pin "2") (pinfunction "2_2") (pintype "passive"))
    )
    (net (code "7") (name "/col7") (class "Default")
      (node (ref "S207") (pin "2") (pinfunction "2_2") (pintype "passive"))
      (node (ref "S221") (pin "2") (pinfunction "2_2") (pintype "passive"))
      (node (ref "S235") (pin "2") (pinfunction "2_2") (pintype "passive"))
      (node (ref "S249") (pin "2") (pinfunction "2_2") (pintype "passive"))
      (node (ref "S262") (pin "1") (pinfunction "1_1") (pintype "passive"))
    )
    (net (code "8") (name "/col8") (class "Default")
      (node (ref "S208") (pin "2") (pinfunction "2_2") (pintype "passive"))
      (node (ref "S222") (pin "2") (pinfunction "2_2") (pintype "passive"))
      (node (ref "S236") (pin "2") (pinfunction "2_2") (pintype "passive"))
      (node (ref "S250") (pin "2") (pinfunction "2_2") (pintype "passive"))
    )
    (net (code "9") (name "/col9") (class "Default")
      (node (ref "S209") (pin "2") (pinfunction "2_2") (pintype "passive"))
      (node (ref "S223") (pin "2") (pinfunction "2_2") (pintype "passive"))
      (node (ref "S237") (pin "2") (pinfunction "2_2") (pintype "passive"))
      (node (ref "S251") (pin "2") (pinfunction "2_2") (pintype "passive"))
      (node (ref "S263") (pin "2") (pinfunction "2_2") (pintype "passive"))
    )
    (net (code "10") (name "/col10") (class "Default")
      (node (ref "S210") (pin "2") (pinfunction "2_2") (pintype "passive"))
      (node (ref "S224") (pin "2") (pinfunction "2_2") (pintype "passive"))
      (node (ref "S238") (pin "2") (pinfunction "2_2") (pintype "passive"))
      (node (ref "S252") (pin "2") (pinfunction "2_2") (pintype "passive"))
    )
    (net (code "11") (name "/col11") (class "Default")
      (node (ref "S211") (pin "2") (pinfunction "2_2") (pintype "passive"))
      (node (ref "S225") (pin "2") (pinfunction "2_2") (pintype "passive"))
      (node (ref "S239") (pin "2") (pinfunction "2_2") (pintype "passive"))
      (node (ref "S253") (pin "2") (pinfunction "2_2") (pintype "passive"))
    )
    (net (code "12") (name "/col12") (class "Default")
      (node (ref "S212") (pin "2") (pinfunction "2_2") (pintype "passive"))
      (node (ref "S226") (pin "2") (pinfunction "2_2") (pintype "passive"))
      (node (ref "S240") (pin "2") (pinfunction "2_2") (pintype "passive"))
      (node (ref "S254") (pin "2") (pinfunction "2_2") (pintype "passive"))
      (node (ref "S265") (pin "2") (pinfunction "2_2") (pintype "passive"))
    )
    (net (code "13") (name "/col13") (class "Default")
      (node (ref "S213") (pin "2") (pinfunction "2_2") (pintype "passive"))
      (node (ref "S227") (pin "2") (pinfunction "2_2") (pintype "passive"))
      (node (ref "S228") (pin "2") (pinfunction "2_2") (pintype "passive"))
      (node (ref "S241") (pin "1") (pinfunction "1_1") (pintype "passive"))
      (node (ref "S256") (pin "2") (pinfunction "2_2") (pintype "passive"))
    )
    (net (code "14") (name "/col14") (class "Default")
      (node (ref "S214") (pin "1") (pinfunction "1_1") (pintype "passive"))
      (node (ref "S242") (pin "2") (pinfunction "2_2") (pintype "passive"))
      (node (ref "S259") (pin "1") (pinfunction "1_1") (pintype "passive"))
      (node (ref "S259_1") (pin "2") (pinfunction "2_2") (pintype "passive"))
      (node (ref "S266") (pin "2") (pinfunction "2_2") (pintype "passive"))
      (node (ref "S269") (pin "2") (pinfunction "2_2") (pintype "passive"))
    )
    (net (code "15") (name "/row1") (class "Default")
      (node (ref "D201") (pin "2") (pinfunction "K_2") (pintype "passive"))
      (node (ref "D202") (pin "2") (pinfunction "K_2") (pintype "passive"))
      (node (ref "D203") (pin "2") (pinfunction "K_2") (pintype "passive"))
      (node (ref "D204") (pin "2") (pinfunction "K_2") (pintype "passive"))
      (node (ref "D205") (pin "2") (pinfunction "K_2") (pintype "passive"))
      (node (ref "D206") (pin "2") (pinfunction "K_2") (pintype "passive"))
      (node (ref "D207") (pin "2") (pinfunction "K_2") (pintype "passive"))
      (node (ref "D208") (pin "2") (pinfunction "K_2") (pintype "passive"))
      (node (ref "D209") (pin "2") (pinfunction "K_2") (pintype "passive"))
      (node (ref "D210") (pin "2") (pinfunction "K_2") (pintype "passive"))
      (node (ref "D211") (pin "2") (pinfunction "K_2") (pintype "passive"))
      (node (ref "D212") (pin "2") (pinfunction "K_2") (pintype "passive"))
      (node (ref "D213") (pin "2") (pinfunction "K_2") (pintype "passive"))
      (node (ref "D214") (pin "2") (pinfunction "K_2") (pintype "passive"))
    )
    (net (code "16") (name "/row2") (class "Default")
      (node (ref "D215") (pin "2") (pinfunction "K_2") (pintype "passive"))
      (node (ref "D216") (pin "2") (pinfunction "K_2") (pintype "passive"))
      (node (ref "D217") (pin "2") (pinfunction "K_2") (pintype "passive"))
      (node (ref "D218") (pin "2") (pinfunction "K_2") (pintype "passive"))
      (node (ref "D219") (pin "2") (pinfunction "K_2") (pintype "passive"))
      (node (ref "D220") (pin "2") (pinfunction "K_2") (pintype "passive"))
      (node (ref "D221") (pin "2") (pinfunction "K_2") (pintype "passive"))
      (node (ref "D222") (pin "2") (pinfunction "K_2") (pintype "passive"))
      (node (ref "D223") (pin "2") (pinfunction "K_2") (pintype "passive"))
      (node (ref "D224") (pin "2") (pinfunction "K_2") (pintype "passive"))
      (node (ref "D225") (pin "2") (pinfunction "K_2") (pintype "passive"))
      (node (ref "D226") (pin "2") (pinfunction "K_2") (pintype "passive"))
      (node (ref "D227") (pin "2") (pinfunction "K_2") (pintype "passive"))
      (node (ref "D228") (pin "2") (pinfunction "K_2") (pintype "passive"))
    )
    (net (code "17") (name "/row3") (class "Default")
      (node (ref "D229") (pin "2") (pinfunction "K_2") (pintype "passive"))
      (node (ref "D230") (pin "2") (pinfunction "K_2") (pintype "passive"))
      (node (ref "D231") (pin "2") (pinfunction "K_2") (pintype "passive"))
      (node (ref "D232") (pin "2") (pinfunction "K_2") (pintype "passive"))
      (node (ref "D233") (pin "2") (pinfunction "K_2") (pintype "passive"))
      (node (ref "D234") (pin "2") (pinfunction "K_2") (pintype "passive"))
      (node (ref "D235") (pin "2") (pinfunction "K_2") (pintype "passive"))
      (node (ref "D236") (pin "2") (pinfunction "K_2") (pintype "passive"))
      (node (ref "D237") (pin "2") (pinfunction "K_2") (pintype "passive"))
      (node (ref "D238") (pin "2") (pinfunction "K_2") (pintype "passive"))
      (node (ref "D239") (pin "2") (pinfunction "K_2") (pintype "passive"))
      (node (ref "D240") (pin "2") (pinfunction "K_2") (pintype "passive"))
      (node (ref "D241") (pin "2") (pinfunction "K_2") (pintype "passive"))
      (node (ref "D242") (pin "2") (pinfunction "K_2") (pintype "passive"))
    )
    (net (code "18") (name "/row4") (class "Default")
      (node (ref "D243") (pin "2") (pinfunction "K_2") (pintype "passive"))
      (node (ref "D244") (pin "2") (pinfunction "K_2") (pintype "passive"))
      (node (ref "D245") (pin "2") (pinfunction "K_2") (pintype "passive"))
      (node (ref "D246") (pin "2") (pinfunction "K_2") (pintype "passive"))
      (node (ref "D247") (pin "2") (pinfunction "K_2") (pintype "passive"))
      (node (ref "D248") (pin "2") (pinfunction "K_2") (pintype "passive"))
      (node (ref "D249") (pin "2") (pinfunction "K_2") (pintype "passive"))
      (node (ref "D250") (pin "2") (pinfunction "K_2") (pintype "passive"))
      (node (ref "D251") (pin "2") (pinfunction "K_2") (pintype "passive"))
      (node (ref "D252") (pin "2") (pinfunction "K_2") (pintype "passive"))
      (node (ref "D253") (pin "2") (pinfunction "K_2") (pintype "passive"))
      (node (ref "D254") (pin "2") (pinfunction "K_2") (pintype "passive"))
      (node (ref "D255") (pin "2") (pinfunction "K_2") (pintype "passive"))
      (node (ref "D256") (pin "2") (pinfunction "K_2") (pintype "passive"))
    )
    (net (code "19") (name "/row5") (class "Default")
      (node (ref "D257") (pin "2") (pinfunction "K_2") (pintype "passive"))
      (node (ref "D258") (pin "2") (pinfunction "K_2") (pintype "passive"))
      (node (ref "D260") (pin "2") (pinfunction "K_2") (pintype "passive"))
      (node (ref "D261") (pin "2") (pinfunction "K_2") (pintype "passive"))
      (node (ref "D262") (pin "2") (pinfunction "K_2") (pintype "passive"))
      (node (ref "D263") (pin "2") (pinfunction "K_2") (pintype "passive"))
      (node (ref "D264") (pin "2") (pinfunction "K_2") (pintype "passive"))
      (node (ref "D265") (pin "2") (pinfunction "K_2") (pintype "passive"))
      (node (ref "D266") (pin "2") (pinfunction "K_2") (pintype "passive"))
    )
    (net (code "20") (name "Net-(D201-A)") (class "Default")
      (node (ref "D201") (pin "1") (pinfunction "A_1") (pintype "passive"))
      (node (ref "S201") (pin "1") (pinfunction "1_1") (pintype "passive"))
    )
    (net (code "21") (name "Net-(D202-A)") (class "Default")
      (node (ref "D202") (pin "1") (pinfunction "A_1") (pintype "passive"))
      (node (ref "S202") (pin "1") (pinfunction "1_1") (pintype "passive"))
    )
    (net (code "22") (name "Net-(D203-A)") (class "Default")
      (node (ref "D203") (pin "1") (pinfunction "A_1") (pintype "passive"))
      (node (ref "S203") (pin "1") (pinfunction "1_1") (pintype "passive"))
    )
    (net (code "23") (name "Net-(D204-A)") (class "Default")
      (node (ref "D204") (pin "1") (pinfunction "A_1") (pintype "passive"))
      (node (ref "S204") (pin "1") (pinfunction "1_1") (pintype "passive"))
    )
    (net (code "24") (name "Net-(D205-A)") (class "Default")
      (node (ref "D205") (pin "1") (pinfunction "A_1") (pintype "passive"))
      (node (ref "S205") (pin "1") (pinfunction "1_1") (pintype "passive"))
    )
    (net (code "25") (name "Net-(D206-A)") (class "Default")
      (node (ref "D206") (pin "1") (pinfunction "A_1") (pintype "passive"))
      (node (ref "S206") (pin "1") (pinfunction "1_1") (pintype "passive"))
    )
    (net (code "26") (name "Net-(D207-A)") (class "Default")
      (node (ref "D207") (pin "1") (pinfunction "A_1") (pintype "passive"))
      (node (ref "S207") (pin "1") (pinfunction "1_1") (pintype "passive"))
    )
    (net (code "27") (name "Net-(D208-A)") (class "Default")
      (node (ref "D208") (pin "1") (pinfunction "A_1") (pintype "passive"))
      (node (ref "S208") (pin "1") (pinfunction "1_1") (pintype "passive"))
    )
    (net (code "28") (name "Net-(D209-A)") (class "Default")
      (node (ref "D209") (pin "1") (pinfunction "A_1") (pintype "passive"))
      (node (ref "S209") (pin "1") (pinfunction "1_1") (pintype "passive"))
    )
    (net (code "29") (name "Net-(D210-A)") (class "Default")
      (node (ref "D210") (pin "1") (pinfunction "A_1") (pintype "passive"))
      (node (ref "S210") (pin "1") (pinfunction "1_1") (pintype "passive"))
    )
    (net (code "30") (name "Net-(D211-A)") (class "Default")
      (node (ref "D211") (pin "1") (pinfunction "A_1") (pintype "passive"))
      (node (ref "S211") (pin "1") (pinfunction "1_1") (pintype "passive"))
    )
    (net (code "31") (name "Net-(D212-A)") (class "Default")
      (node (ref "D212") (pin "1") (pinfunction "A_1") (pintype "passive"))
      (node (ref "S212") (pin "1") (pinfunction "1_1") (pintype "passive"))
    )
    (net (code "32") (name "Net-(D213-A)") (class "Default")
      (node (ref "D213") (pin "1") (pinfunction "A_1") (pintype "passive"))
      (node (ref "S213") (pin "1") (pinfunction "1_1") (pintype "passive"))
    )
    (net (code "33") (name "Net-(D214-A)") (class "Default")
      (node (ref "D214") (pin "1") (pinfunction "A_1") (pintype "passive"))
      (node (ref "S214") (pin "2") (pinfunction "2_2") (pintype "passive"))
    )
    (net (code "34") (name "Net-(D215-A)") (class "Default")
      (node (ref "D215") (pin "1") (pinfunction "A_1") (pintype "passive"))
      (node (ref "S215") (pin "1") (pinfunction "1_1") (pintype "passive"))
    )
    (net (code "35") (name "Net-(D216-A)") (class "Default")
      (node (ref "D216") (pin "1") (pinfunction "A_1") (pintype "passive"))
      (node (ref "S216") (pin "1") (pinfunction "1_1") (pintype "passive"))
    )
    (net (code "36") (name "Net-(D217-A)") (class "Default")
      (node (ref "D217") (pin "1") (pinfunction "A_1") (pintype "passive"))
      (node (ref "S217") (pin "1") (pinfunction "1_1") (pintype "passive"))
    )
    (net (code "37") (name "Net-(D218-A)") (class "Default")
      (node (ref "D218") (pin "1") (pinfunction "A_1") (pintype "passive"))
      (node (ref "S218") (pin "1") (pinfunction "1_1") (pintype "passive"))
    )
    (net (code "38") (name "Net-(D219-A)") (class "Default")
      (node (ref "D219") (pin "1") (pinfunction "A_1") (pintype "passive"))
      (node (ref "S219") (pin "1") (pinfunction "1_1") (pintype "passive"))
    )
    (net (code "39") (name "Net-(D220-A)") (class "Default")
      (node (ref "D220") (pin "1") (pinfunction "A_1") (pintype "passive"))
      (node (ref "S220") (pin "1") (pinfunction "1_1") (pintype "passive"))
    )
    (net (code "40") (name "Net-(D221-A)") (class "Default")
      (node (ref "D221") (pin "1") (pinfunction "A_1") (pintype "passive"))
      (node (ref "S221") (pin "1") (pinfunction "1_1") (pintype "passive"))
    )
    (net (code "41") (name "Net-(D222-A)") (class "Default")
      (node (ref "D222") (pin "1") (pinfunction "A_1") (pintype "passive"))
      (node (ref "S222") (pin "1") (pinfunction "1_1") (pintype "passive"))
    )
    (net (code "42") (name "Net-(D223-A)") (class "Default")
      (node (ref "D223") (pin "1") (pinfunction "A_1") (pintype "passive"))
      (node (ref "S223") (pin "1") (pinfunction "1_1") (pintype "passive"))
    )
    (net (code "43") (name "Net-(D224-A)") (class "Default")
      (node (ref "D224") (pin "1") (pinfunction "A_1") (pintype "passive"))
      (node (ref "S224") (pin "1") (pinfunction "1_1") (pintype "passive"))
    )
    (net (code "44") (name "Net-(D225-A)") (class "Default")
      (node (ref "D225") (pin "1") (pinfunction "A_1") (pintype "passive"))
      (node (ref "S225") (pin "1") (pinfunction "1_1") (pintype "passive"))
    )
    (net (code "45") (name "Net-(D226-A)") (class "Default")
      (node (ref "D226") (pin "1") (pinfunction "A_1") (pintype "passive"))
      (node (ref "S226") (pin "1") (pinfunction "1_1") (pintype "passive"))
    )
    (net (code "46") (name "Net-(D227-A)") (class "Default")
      (node (ref "D227") (pin "1") (pinfunction "A_1") (pintype "passive"))
      (node (ref "S227") (pin "1") (pinfunction "1_1") (pintype "passive"))
    )
    (net (code "47") (name "Net-(D228-A)") (class "Default")
      (node (ref "D228") (pin "1") (pinfunction "A_1") (pintype "passive"))
      (node (ref "S259") (pin "2") (pinfunction "2_2") (pintype "passive"))
      (node (ref "S259_1") (pin "1") (pinfunction "1_1") (pintype "passive"))
    )
    (net (code "48") (name "Net-(D229-A)") (class "Default")
      (node (ref "D229") (pin "1") (pinfunction "A_1") (pintype "passive"))
      (node (ref "S229") (pin "1") (pinfunction "1_1") (pintype "passive"))
      (node (ref "S229_1") (pin "2") (pinfunction "2_2") (pintype "passive"))
    )
    (net (code "49") (name "Net-(D230-A)") (class "Default")
      (node (ref "D230") (pin "1") (pinfunction "A_1") (pintype "passive"))
      (node (ref "S230") (pin "1") (pinfunction "1_1") (pintype "passive"))
    )
    (net (code "50") (name "Net-(D231-A)") (class "Default")
      (node (ref "D231") (pin "1") (pinfunction "A_1") (pintype "passive"))
      (node (ref "S231") (pin "1") (pinfunction "1_1") (pintype "passive"))
    )
    (net (code "51") (name "Net-(D232-A)") (class "Default")
      (node (ref "D232") (pin "1") (pinfunction "A_1") (pintype "passive"))
      (node (ref "S232") (pin "1") (pinfunction "1_1") (pintype "passive"))
    )
    (net (code "52") (name "Net-(D233-A)") (class "Default")
      (node (ref "D233") (pin "1") (pinfunction "A_1") (pintype "passive"))
      (node (ref "S233") (pin "1") (pinfunction "1_1") (pintype "passive"))
    )
    (net (code "53") (name "Net-(D234-A)") (class "Default")
      (node (ref "D234") (pin "1") (pinfunction "A_1") (pintype "passive"))
      (node (ref "S234") (pin "1") (pinfunction "1_1") (pintype "passive"))
    )
    (net (code "54") (name "Net-(D235-A)") (class "Default")
      (node (ref "D235") (pin "1") (pinfunction "A_1") (pintype "passive"))
      (node (ref "S235") (pin "1") (pinfunction "1_1") (pintype "passive"))
    )
    (net (code "55") (name "Net-(D236-A)") (class "Default")
      (node (ref "D236") (pin "1") (pinfunction "A_1") (pintype "passive"))
      (node (ref "S236") (pin "1") (pinfunction "1_1") (pintype "passive"))
    )
    (net (code "56") (name "Net-(D237-A)") (class "Default")
      (node (ref "D237") (pin "1") (pinfunction "A_1") (pintype "passive"))
      (node (ref "S237") (pin "1") (pinfunction "1_1") (pintype "passive"))
    )
    (net (code "57") (name "Net-(D238-A)") (class "Default")
      (node (ref "D238") (pin "1") (pinfunction "A_1") (pintype "passive"))
      (node (ref "S238") (pin "1") (pinfunction "1_1") (pintype "passive"))
    )
    (net (code "58") (name "Net-(D239-A)") (class "Default")
      (node (ref "D239") (pin "1") (pinfunction "A_1") (pintype "passive"))
      (node (ref "S239") (pin "1") (pinfunction "1_1") (pintype "passive"))
    )
    (net (code "59") (name "Net-(D240-A)") (class "Default")
      (node (ref "D240") (pin "1") (pinfunction "A_1") (pintype "passive"))
      (node (ref "S240") (pin "1") (pinfunction "1_1") (pintype "passive"))
    )
    (net (code "60") (name "Net-(D241-A)") (class "Default")
      (node (ref "D241") (pin "1") (pinfunction "A_1") (pintype "passive"))
      (node (ref "S242") (pin "1") (pinfunction "1_1") (pintype "passive"))
    )
    (net (code "61") (name "Net-(D242-A)") (class "Default")
      (node (ref "D242") (pin "1") (pinfunction "A_1") (pintype "passive"))
      (node (ref "S228") (pin "1") (pinfunction "1_1") (pintype "passive"))
    )
    (net (code "62") (name "Net-(D243-A)") (class "Default")
      (node (ref "D243") (pin "1") (pinfunction "A_1") (pintype "passive"))
      (node (ref "S243") (pin "1") (pinfunction "1_1") (pintype "passive"))
    )
    (net (code "63") (name "Net-(D244-A)") (class "Default")
      (node (ref "D244") (pin "1") (pinfunction "A_1") (pintype "passive"))
      (node (ref "S244") (pin "2") (pinfunction "2_2") (pintype "passive"))
    )
    (net (code "64") (name "Net-(D245-A)") (class "Default")
      (node (ref "D245") (pin "1") (pinfunction "A_1") (pintype "passive"))
      (node (ref "S245") (pin "1") (pinfunction "1_1") (pintype "passive"))
    )
    (net (code "65") (name "Net-(D246-A)") (class "Default")
      (node (ref "D246") (pin "1") (pinfunction "A_1") (pintype "passive"))
      (node (ref "S246") (pin "1") (pinfunction "1_1") (pintype "passive"))
    )
    (net (code "66") (name "Net-(D247-A)") (class "Default")
      (node (ref "D247") (pin "1") (pinfunction "A_1") (pintype "passive"))
      (node (ref "S247") (pin "1") (pinfunction "1_1") (pintype "passive"))
    )
    (net (code "67") (name "Net-(D248-A)") (class "Default")
      (node (ref "D248") (pin "1") (pinfunction "A_1") (pintype "passive"))
      (node (ref "S248") (pin "1") (pinfunction "1_1") (pintype "passive"))
    )
    (net (code "68") (name "Net-(D249-A)") (class "Default")
      (node (ref "D249") (pin "1") (pinfunction "A_1") (pintype "passive"))
      (node (ref "S249") (pin "1") (pinfunction "1_1") (pintype "passive"))
    )
    (net (code "69") (name "Net-(D250-A)") (class "Default")
      (node (ref "D250") (pin "1") (pinfunction "A_1") (pintype "passive"))
      (node (ref "S250") (pin "1") (pinfunction "1_1") (pintype "passive"))
    )
    (net (code "70") (name "Net-(D251-A)") (class "Default")
      (node (ref "D251") (pin "1") (pinfunction "A_1") (pintype "passive"))
      (node (ref "S251") (pin "1") (pinfunction "1_1") (pintype "passive"))
    )
    (net (code "71") (name "Net-(D252-A)") (class "Default")
      (node (ref "D252") (pin "1") (pinfunction "A_1") (pintype "passive"))
      (node (ref "S252") (pin "1") (pinfunction "1_1") (pintype "passive"))
    )
    (net (code "72") (name "Net-(D253-A)") (class "Default")
      (node (ref "D253") (pin "1") (pinfunction "A_1") (pintype "passive"))
      (node (ref "S253") (pin "1") (pinfunction "1_1") (pintype "passive"))
    )
    (net (code "73") (name "Net-(D254-A)") (class "Default")
      (node (ref "D254") (pin "1") (pinfunction "A_1") (pintype "passive"))
      (node (ref "S254") (pin "1") (pinfunction "1_1") (pintype "passive"))
    )
    (net (code "74") (name "Net-(D255-A)") (class "Default")
      (node (ref "D255") (pin "1") (pinfunction "A_1") (pintype "passive"))
      (node (ref "S256") (pin "1") (pinfunction "1_1") (pintype "passive"))
    )
    (net (code "75") (name "Net-(D256-A)") (class "Default")
      (node (ref "D256") (pin "1") (pinfunction "A_1") (pintype "passive"))
      (node (ref "S269") (pin "1") (pinfunction "1_1") (pintype "passive"))
    )
    (net (code "76") (name "Net-(D257-A)") (class "Default")
      (node (ref "D257") (pin "1") (pinfunction "A_1") (pintype "passive"))
      (node (ref "S257") (pin "2") (pinfunction "2_2") (pintype "passive"))
    )
    (net (code "77") (name "Net-(D258-A)") (class "Default")
      (node (ref "D258") (pin "1") (pinfunction "A_1") (pintype "passive"))
      (node (ref "S258") (pin "1") (pinfunction "1_1") (pintype "passive"))
    )
    (net (code "78") (name "Net-(D260-A)") (class "Default")
      (node (ref "D260") (pin "1") (pinfunction "A_1") (pintype "passive"))
      (node (ref "S260") (pin "1") (pinfunction "1_1") (pintype "passive"))
    )
    (net (code "79") (name "Net-(D261-A)") (class "Default")
      (node (ref "D261") (pin "1") (pinfunction "A_1") (pintype "passive"))
      (node (ref "S261") (pin "1") (pinfunction "1_1") (pintype "passive"))
    )
    (net (code "80") (name "Net-(D262-A)") (class "Default")
      (node (ref "D262") (pin "1") (pinfunction "A_1") (pintype "passive"))
      (node (ref "S262") (pin "2") (pinfunction "2_2") (pintype "passive"))
    )
    (net (code "81") (name "Net-(D263-A)") (class "Default")
      (node (ref "D263") (pin "1") (pinfunction "A_1") (pintype "passive"))
      (node (ref "S263") (pin "1") (pinfunction "1_1") (pintype "passive"))
    )
    (net (code "82") (name "Net-(D264-A)") (class "Default")
      (node (ref "D264") (pin "1") (pinfunction "A_1") (pintype "passive"))
      (node (ref "S265") (pin "1") (pinfunction "1_1") (pintype "passive"))
    )
    (net (code "83") (name "Net-(D265-A)") (class "Default")
      (node (ref "D265") (pin "1") (pinfunction "A_1") (pintype "passive"))
      (node (ref "S241") (pin "2") (pinfunction "2_2") (pintype "passive"))
    )
    (net (code "84") (name "Net-(D266-A)") (class "Default")
      (node (ref "D266") (pin "1") (pinfunction "A_1") (pintype "passive"))
      (node (ref "S266") (pin "1") (pinfunction "1_1") (pintype "passive"))
    )
    (net (code "85") (name "unconnected-(STAB1-Pad1)") (class "Default")
      (node (ref "STAB1") (pin "1") (pinfunction "1_1") (pintype "passive"))
    )
    (net (code "86") (name "unconnected-(STAB2-Pad1)") (class "Default")
      (node (ref "STAB2") (pin "1") (pinfunction "1_1") (pintype "passive"))
    )
    (net (code "87") (name "unconnected-(STAB3-Pad1)") (class "Default")
      (node (ref "STAB3") (pin "1") (pinfunction "1_1") (pintype "passive"))
    )
    (net (code "88") (name "unconnected-(STAB4-Pad1)") (class "Default")
      (node (ref "STAB4") (pin "1") (pinfunction "1_1") (pintype "passive"))
    )
    (net (code "89") (name "unconnected-(STAB5-Pad1)") (class "Default")
      (node (ref "STAB5") (pin "1") (pinfunction "1_1") (pintype "passive"))
    )
    (net (code "90") (name "unconnected-(STAB6-Pad1)") (class "Default")
      (node (ref "STAB6") (pin "1") (pinfunction "1_1") (pintype "passive"))
    )
  )
)
